# differential_lowpass.net
KiCad netlist of a schematic drawn in Altium Designer
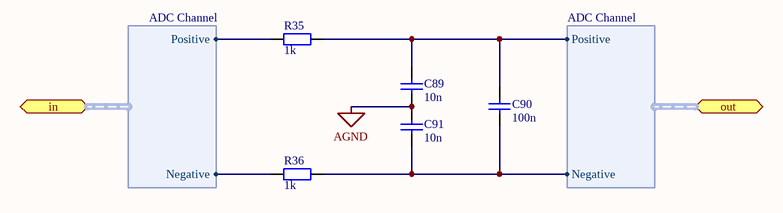
[diagram p0: differential_lowpass.SchDoc]

(export (version "E")
  (design (tool "Eeschema 10.0.6"))
  (components
    (comp (ref "C89")
      (value "10n")
      (footprint "C0603")
      (description "Generic capacitor")
      (libsource (lib "GG") (part "Cap"))
    )
    (comp (ref "C90")
      (value "100n")
      (footprint "C0603")
      (description "Generic capacitor")
      (libsource (lib "GG") (part "Cap"))
    )
    (comp (ref "C91")
      (value "10n")
      (footprint "C0603")
      (description "Generic capacitor")
      (libsource (lib "GG") (part "Cap"))
    )
    (comp (ref "R35")
      (value "1k")
      (footprint "0603")
      (description "Generic resistor")
      (libsource (lib "GG") (part "Res"))
    )
    (comp (ref "R36")
      (value "1k")
      (footprint "0603")
      (description "Generic resistor")
      (libsource (lib "GG") (part "Res"))
    )
  )
  (nets
    (net (code "4") (name "AGND") (class "Default")
      (node (ref "C89") (pin "2") (pinfunction "2_2") (pintype "passive"))
      (node (ref "C91") (pin "1") (pinfunction "1_1") (pintype "passive"))
    )
    (net (code "5") (name "Net-(C89-Pad1)") (class "Default")
      (node (ref "C89") (pin "1") (pinfunction "1_1") (pintype "passive"))
      (node (ref "C90") (pin "1") (pinfunction "1_1") (pintype "passive"))
      (node (ref "R35") (pin "2") (pinfunction "2_2") (pintype "passive"))
    )
    (net (code "6") (name "Net-(C90-Pad2)") (class "Default")
      (node (ref "C90") (pin "2") (pinfunction "2_2") (pintype "passive"))
      (node (ref "C91") (pin "2") (pinfunction "2_2") (pintype "passive"))
      (node (ref "R36") (pin "2") (pinfunction "2_2") (pintype "passive"))
    )
    (net (code "7") (name "unconnected-(R35-Pad1)") (class "Default")
      (node (ref "R35") (pin "1") (pinfunction "1_1") (pintype "passive"))
    )
    (net (code "8") (name "unconnected-(R36-Pad1)") (class "Default")
      (node (ref "R36") (pin "1") (pinfunction "1_1") (pintype "passive"))
    )
  )
)
